# Power.net
KiCad netlist of a schematic drawn in Altium Designer
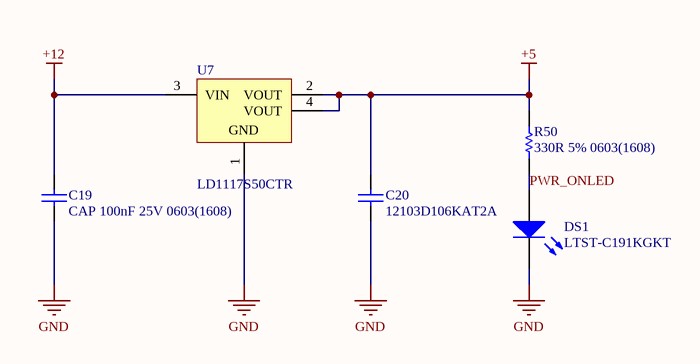
[diagram p0: Power.SchDoc]

(export (version "E")
  (design (tool "Eeschema 10.0.6"))
  (components
    (comp (ref "C19")
      (value "CAP 100nF 25V 0603(1608)")
      (footprint "CAPC0603(1608)100_N")
      (description "CAP 100nF 25V ±5% 0603 (1608 Metric) Thickness 1mm SMD")
      (fields (field (name "TOLERANCE") "Â±5%"))
      (libsource (lib "Altium Content Vault") (part "CAP"))
    )
    (comp (ref "C20")
      (value "12103D106KAT2A")
      (footprint "CAPC3225X279X50LL20T25")
      (description "Chip Capacitor, 10 uF, +/- 10%, 25 V, -55 to 85 degC, 1210 (3225 Metric), RoHS, Tape and Reel")
      (fields (field (name "TOLERANCE") "±10%") (field (name "MANUFACTURER") "AVX"))
      (libsource (lib "Altium Content Vault") (part "CAP-NP-2"))
    )
    (comp (ref "DS1")
      (value "LTST-C191KGKT")
      (footprint "LITE-ON-LTST-C191KRKT-2_V")
      (description "Chip LED, Green, 574 nm, 40 pF, -55 to 85 degC, 2-Pin SMD, RoHS, Tape and Reel")
      (fields (field (name "MANUFACTURER") "Lite-On"))
      (libsource (lib "Altium Content Vault") (part "LED-AK-2"))
    )
    (comp (ref "R50")
      (value "330R 5% 0603(1608)")
      (footprint "RESC0603(1608)_L")
      (description "330R 0.1W 5% 0603 (1608 Metric)  SMD")
      (fields (field (name "TOLERANCE") "5 %") (field (name "POWER") "0.1 W"))
      (libsource (lib "Altium Content Vault") (part "RES"))
    )
    (comp (ref "U7")
      (value "LD1117S50CTR")
      (footprint "SOT-223_N")
      (description "Fixed Low Drop Positive Voltage Regulator, 5V, 4-Pin SOT-223, Tape and Reel")
      (libsource (lib "Altium Content Vault") (part "PM-REG-LD1117-SOT4"))
    )
  )
  (nets
    (net (code "1") (name "+5") (class "Default")
      (node (ref "C20") (pin "2") (pinfunction "2_2") (pintype "passive"))
      (node (ref "R50") (pin "1") (pinfunction "1_1") (pintype "passive"))
      (node (ref "U7") (pin "2") (pinfunction "VOUT_2") (pintype "power_in"))
      (node (ref "U7") (pin "4") (pinfunction "VOUT_4") (pintype "power_in"))
    )
    (net (code "2") (name "+12") (class "Default")
      (node (ref "C19") (pin "2") (pinfunction "2_2") (pintype "passive"))
      (node (ref "U7") (pin "3") (pinfunction "VIN_3") (pintype "power_in"))
    )
    (net (code "3") (name "/PWR_ONLED") (class "Default")
      (node (ref "DS1") (pin "1") (pinfunction "A_1") (pintype "passive"))
      (node (ref "R50") (pin "2") (pinfunction "2_2") (pintype "passive"))
    )
    (net (code "4") (name "GND") (class "Default")
      (node (ref "C19") (pin "1") (pinfunction "1_1") (pintype "passive"))
      (node (ref "C20") (pin "1") (pinfunction "1_1") (pintype "passive"))
      (node (ref "DS1") (pin "2") (pinfunction "K_2") (pintype "passive"))
      (node (ref "U7") (pin "1") (pinfunction "GND_1") (pintype "power_in"))
    )
  )
)
